# Sheet2.net
KiCad netlist of a schematic drawn in Altium Designer
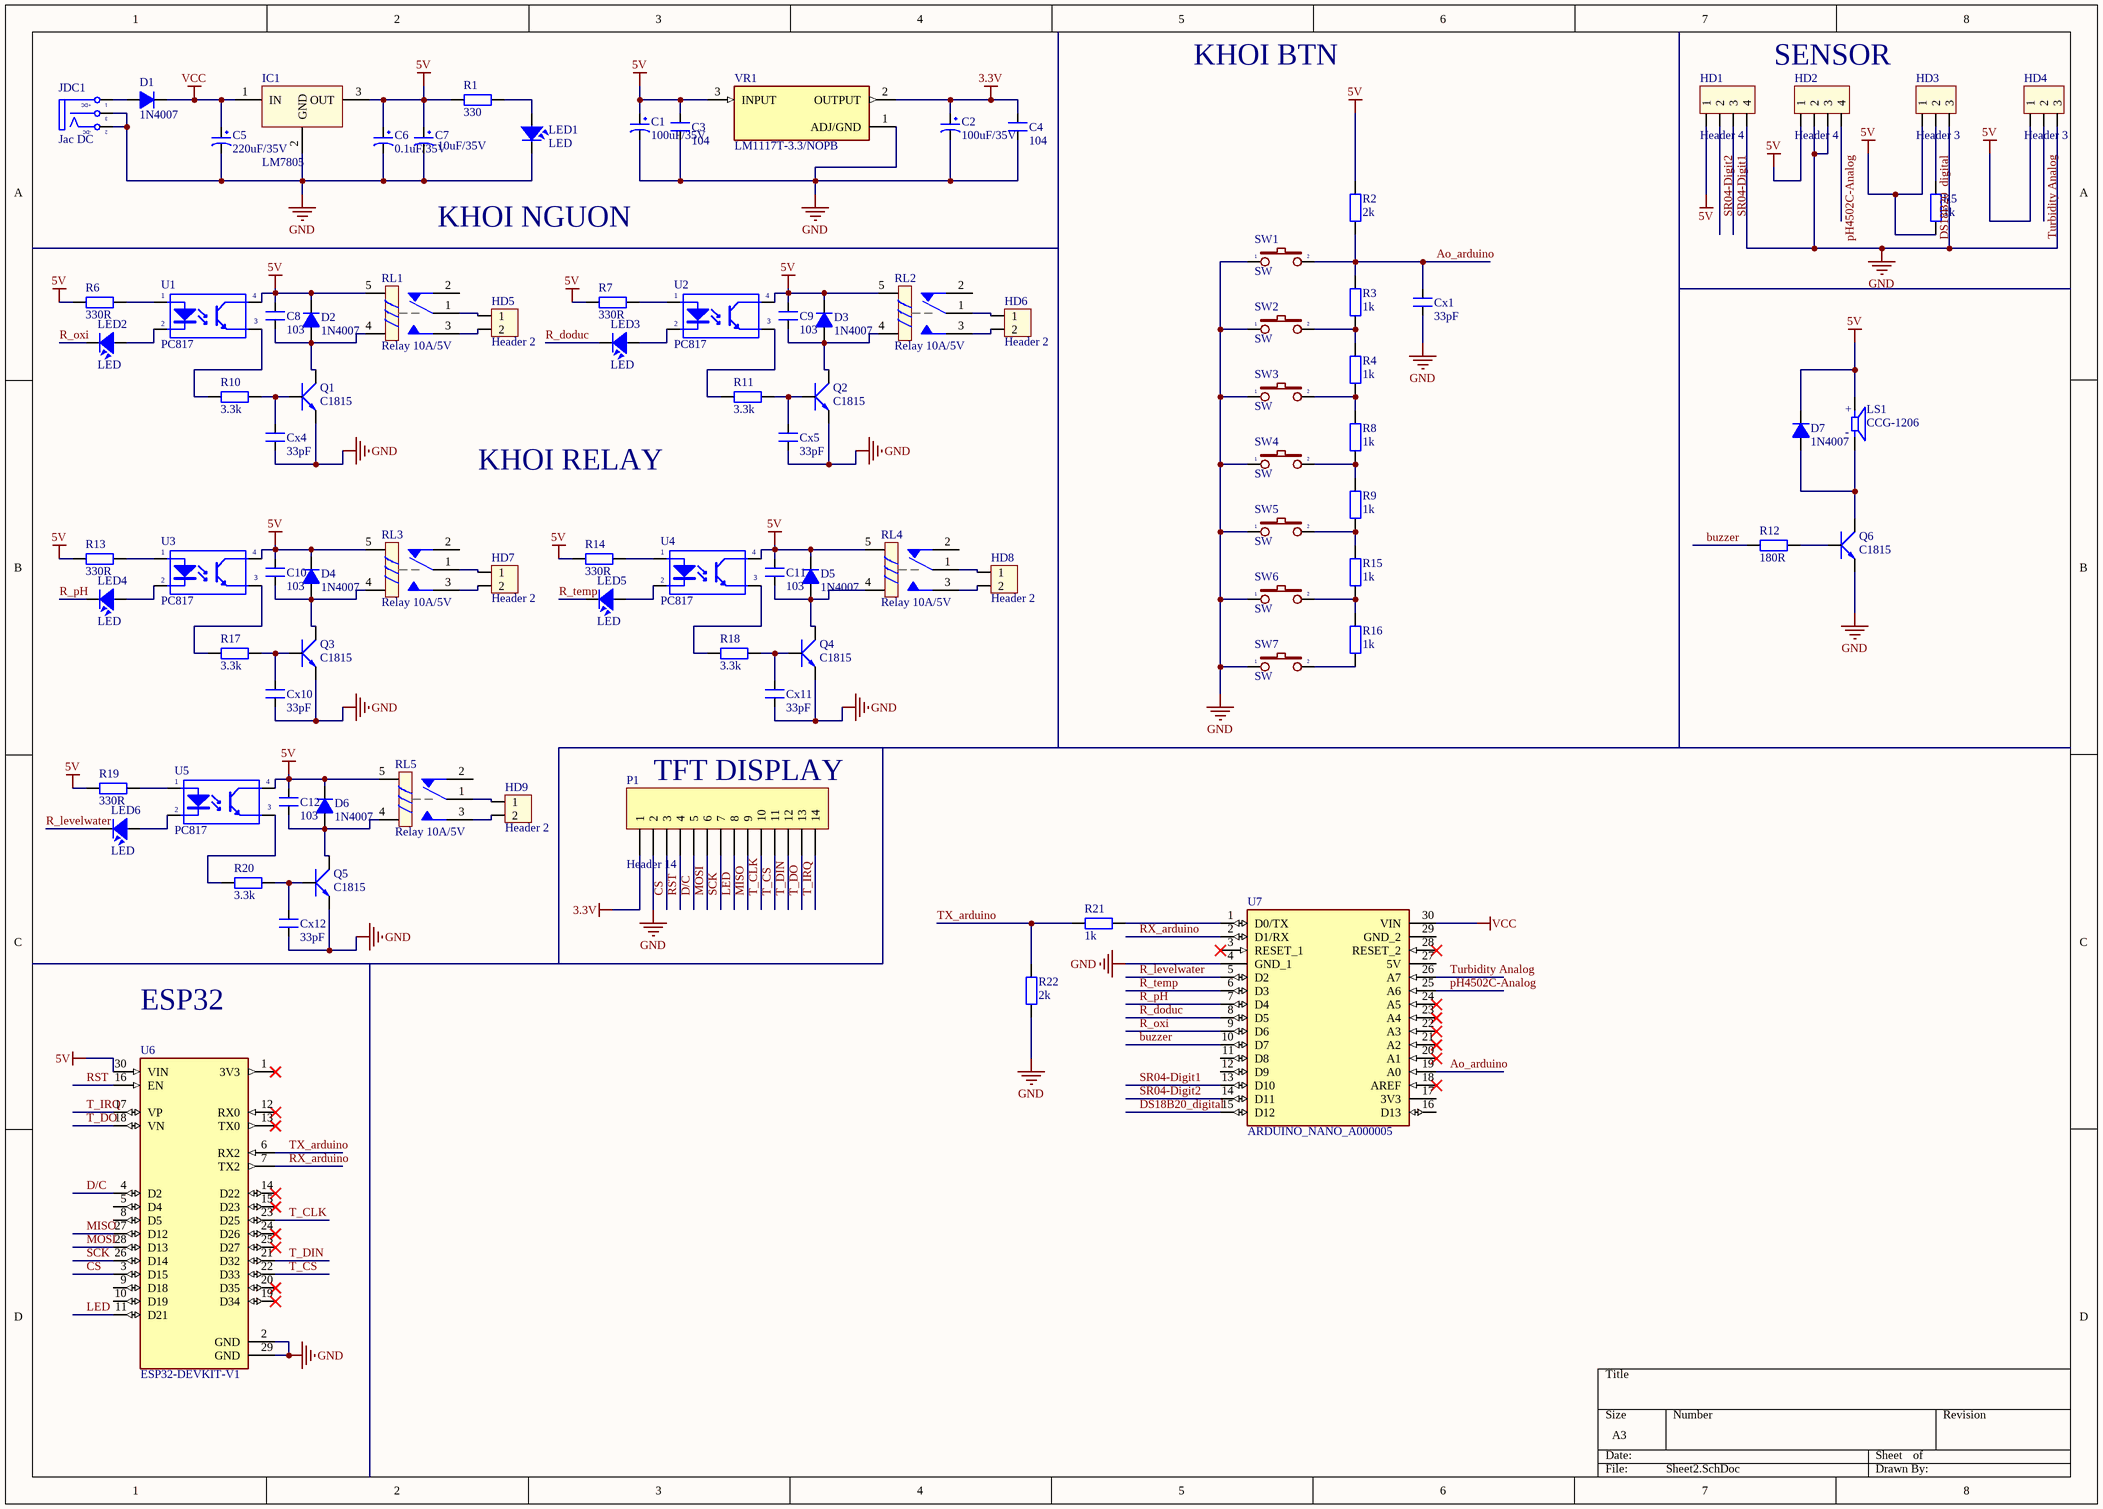
[diagram p0: Sheet2.SchDoc]

(export (version "E")
  (design (tool "Eeschema 10.0.6"))
  (components
    (comp (ref "C1")
      (value "100uF/35V")
      (footprint "CP1.5/3.4")
      (description "Cap 100uF/35V - 470uF/16V")
      (libsource (lib "syhaunguyen") (part "CP3"))
    )
    (comp (ref "C2")
      (value "100uF/35V")
      (footprint "CP1.5/3.4")
      (description "Cap 100uF/35V - 470uF/16V")
      (libsource (lib "syhaunguyen") (part "CP3"))
    )
    (comp (ref "C3")
      (value "104")
      (footprint "CN2")
      (description "Cap np 104 => 105pF")
      (libsource (lib "syhaunguyen") (part "CN2"))
    )
    (comp (ref "C4")
      (value "104")
      (footprint "CN2")
      (description "Cap np 104 => 105pF")
      (libsource (lib "syhaunguyen") (part "CN2"))
    )
    (comp (ref "C5")
      (value "220uF/35V")
      (footprint "CP1.5/3.4")
      (description "Cap 100uF/35V - 470uF/16V")
      (libsource (lib "syhaunguyen") (part "CP3"))
    )
    (comp (ref "C6")
      (value "0.1uF/35V")
      (footprint "CP1.5/3.4")
      (description "Cap 100uF/35V - 470uF/16V")
      (libsource (lib "syhaunguyen") (part "CP3"))
    )
    (comp (ref "C7")
      (value "10uF/35V")
      (footprint "CP1.5/3.4")
      (description "Cap 100uF/35V - 470uF/16V")
      (libsource (lib "syhaunguyen") (part "CP3"))
    )
    (comp (ref "C8")
      (value "103")
      (footprint "CN1.5")
      (description "Cap np 682pF => 104pF")
      (libsource (lib "syhaunguyen") (part "CN1.5"))
    )
    (comp (ref "C9")
      (value "103")
      (footprint "CN1.5")
      (description "Cap np 682pF => 104pF")
      (libsource (lib "syhaunguyen") (part "CN1.5"))
    )
    (comp (ref "C10")
      (value "103")
      (footprint "CN1.5")
      (description "Cap np 682pF => 104pF")
      (libsource (lib "syhaunguyen") (part "CN1.5"))
    )
    (comp (ref "C11")
      (value "103")
      (footprint "CN1.5")
      (description "Cap np 682pF => 104pF")
      (libsource (lib "syhaunguyen") (part "CN1.5"))
    )
    (comp (ref "C12")
      (value "103")
      (footprint "CN1.5")
      (description "Cap np 682pF => 104pF")
      (libsource (lib "syhaunguyen") (part "CN1.5"))
    )
    (comp (ref "Cx1")
      (value "33pF")
      (footprint "CN1")
      (description "Cremic For Xtal 1pF => 100pF")
      (libsource (lib "syhaunguyen") (part "CN0"))
    )
    (comp (ref "Cx4")
      (value "33pF")
      (footprint "CN1")
      (description "Cremic For Xtal 1pF => 100pF")
      (libsource (lib "syhaunguyen") (part "CN0"))
    )
    (comp (ref "Cx5")
      (value "33pF")
      (footprint "CN1")
      (description "Cremic For Xtal 1pF => 100pF")
      (libsource (lib "syhaunguyen") (part "CN0"))
    )
    (comp (ref "Cx10")
      (value "33pF")
      (footprint "CN1")
      (description "Cremic For Xtal 1pF => 100pF")
      (libsource (lib "syhaunguyen") (part "CN0"))
    )
    (comp (ref "Cx11")
      (value "33pF")
      (footprint "CN1")
      (description "Cremic For Xtal 1pF => 100pF")
      (libsource (lib "syhaunguyen") (part "CN0"))
    )
    (comp (ref "Cx12")
      (value "33pF")
      (footprint "CN1")
      (description "Cremic For Xtal 1pF => 100pF")
      (libsource (lib "syhaunguyen") (part "CN0"))
    )
    (comp (ref "D1")
      (value "1N4007")
      (footprint "D1A")
      (description "Diode 1A")
      (libsource (lib "syhaunguyen") (part "D1A"))
    )
    (comp (ref "D2")
      (value "1N4007")
      (footprint "D1A")
      (description "Diode 1A")
      (libsource (lib "syhaunguyen") (part "D1A"))
    )
    (comp (ref "D3")
      (value "1N4007")
      (footprint "D1A")
      (description "Diode 1A")
      (libsource (lib "syhaunguyen") (part "D1A"))
    )
    (comp (ref "D4")
      (value "1N4007")
      (footprint "D1A")
      (description "Diode 1A")
      (libsource (lib "syhaunguyen") (part "D1A"))
    )
    (comp (ref "D5")
      (value "1N4007")
      (footprint "D1A")
      (description "Diode 1A")
      (libsource (lib "syhaunguyen") (part "D1A"))
    )
    (comp (ref "D6")
      (value "1N4007")
      (footprint "D1A")
      (description "Diode 1A")
      (libsource (lib "syhaunguyen") (part "D1A"))
    )
    (comp (ref "D7")
      (value "1N4007")
      (footprint "D1A")
      (description "Diode 1A")
      (libsource (lib "syhaunguyen") (part "D1A"))
    )
    (comp (ref "HD1")
      (value "Header 4")
      (footprint "HED4")
      (description "Header 4 (Green)")
      (libsource (lib "syhaunguyen") (part "Hed4"))
    )
    (comp (ref "HD2")
      (value "Header 4")
      (footprint "HED4")
      (description "Header 4 (Green)")
      (libsource (lib "syhaunguyen") (part "Hed4"))
    )
    (comp (ref "HD3")
      (value "Header 3")
      (footprint "HED3")
      (description "Header 3 (Green)")
      (libsource (lib "syhaunguyen") (part "Hed3"))
    )
    (comp (ref "HD4")
      (value "Header 3")
      (footprint "HED3")
      (description "Header 3 (Green)")
      (libsource (lib "syhaunguyen") (part "Hed3"))
    )
    (comp (ref "HD5")
      (value "Header 2")
      (footprint "HED2")
      (description "Header 2 (Green)")
      (libsource (lib "syhaunguyen") (part "Hed2"))
    )
    (comp (ref "HD6")
      (value "Header 2")
      (footprint "HED2")
      (description "Header 2 (Green)")
      (libsource (lib "syhaunguyen") (part "Hed2"))
    )
    (comp (ref "HD7")
      (value "Header 2")
      (footprint "HED2")
      (description "Header 2 (Green)")
      (libsource (lib "syhaunguyen") (part "Hed2"))
    )
    (comp (ref "HD8")
      (value "Header 2")
      (footprint "HED2")
      (description "Header 2 (Green)")
      (libsource (lib "syhaunguyen") (part "Hed2"))
    )
    (comp (ref "HD9")
      (value "Header 2")
      (footprint "HED2")
      (description "Header 2 (Green)")
      (libsource (lib "syhaunguyen") (part "Hed2"))
    )
    (comp (ref "IC1")
      (value "LM7805")
      (footprint "QTO-220")
      (description "On ap +, from + 5 to + 24VDC")
      (libsource (lib "syhaunguyen") (part "LM78xx"))
    )
    (comp (ref "JDC1")
      (value "Jac DC")
      (footprint "DC-IN")
      (description "Jac DC input")
      (libsource (lib "syhaunguyen") (part "DCIN"))
    )
    (comp (ref "LED1")
      (value "LED")
      (footprint "LED-3")
      (description "LED Single colour Green and Red")
      (libsource (lib "syhaunguyen") (part "LED"))
    )
    (comp (ref "LED2")
      (value "LED")
      (footprint "LED-3")
      (description "LED Single colour Green and Red")
      (libsource (lib "syhaunguyen") (part "LED"))
    )
    (comp (ref "LED3")
      (value "LED")
      (footprint "LED-3")
      (description "LED Single colour Green and Red")
      (libsource (lib "syhaunguyen") (part "LED"))
    )
    (comp (ref "LED4")
      (value "LED")
      (footprint "LED-3")
      (description "LED Single colour Green and Red")
      (libsource (lib "syhaunguyen") (part "LED"))
    )
    (comp (ref "LED5")
      (value "LED")
      (footprint "LED-3")
      (description "LED Single colour Green and Red")
      (libsource (lib "syhaunguyen") (part "LED"))
    )
    (comp (ref "LED6")
      (value "LED")
      (footprint "LED-3")
      (description "LED Single colour Green and Red")
      (libsource (lib "syhaunguyen") (part "LED"))
    )
    (comp (ref "LS1")
      (value "CCG-1206")
      (footprint "CUI_CCG-1206")
      (description "12 mm, 5 V, 85 dB, Through Hole, Sealed, Magnetic Audio Transducer Buzzer")
      (libsource (lib "CCG-1206") (part "CCG-1206"))
    )
    (comp (ref "P1")
      (value "Header 14")
      (footprint "HDR1X14")
      (description "Header, 14-Pin")
      (fields (field (name "PUBLISHER") "Altium Limited"))
      (libsource (lib "Library AL") (part "Header 14"))
    )
    (comp (ref "Q1")
      (value "C1815")
      (footprint "QTO-92")
      (description "NPN 600mW, ECB")
      (libsource (lib "syhaunguyen") (part "C1815"))
    )
    (comp (ref "Q2")
      (value "C1815")
      (footprint "QTO-92")
      (description "NPN 600mW, ECB")
      (libsource (lib "syhaunguyen") (part "C1815"))
    )
    (comp (ref "Q3")
      (value "C1815")
      (footprint "QTO-92")
      (description "NPN 600mW, ECB")
      (libsource (lib "syhaunguyen") (part "C1815"))
    )
    (comp (ref "Q4")
      (value "C1815")
      (footprint "QTO-92")
      (description "NPN 600mW, ECB")
      (libsource (lib "syhaunguyen") (part "C1815"))
    )
    (comp (ref "Q5")
      (value "C1815")
      (footprint "QTO-92")
      (description "NPN 600mW, ECB")
      (libsource (lib "syhaunguyen") (part "C1815"))
    )
    (comp (ref "Q6")
      (value "C1815")
      (footprint "QTO-92")
      (description "NPN 600mW, ECB")
      (libsource (lib "syhaunguyen") (part "C1815"))
    )
    (comp (ref "R1")
      (value "330")
      (footprint "R1/4W")
      (description "Resistor 1/4W")
      (libsource (lib "syhaunguyen") (part "R1/4W"))
    )
    (comp (ref "R2")
      (value "2k")
      (footprint "R1/4W")
      (description "Resistor 1/4W")
      (libsource (lib "syhaunguyen") (part "R1/4W"))
    )
    (comp (ref "R3")
      (value "1k")
      (footprint "R1/4W")
      (description "Resistor 1/4W")
      (libsource (lib "syhaunguyen") (part "R1/4W"))
    )
    (comp (ref "R4")
      (value "1k")
      (footprint "R1/4W")
      (description "Resistor 1/4W")
      (libsource (lib "syhaunguyen") (part "R1/4W"))
    )
    (comp (ref "R5")
      (value "1k")
      (footprint "R1/4W")
      (description "Resistor 1/4W")
      (libsource (lib "syhaunguyen") (part "R1/4W"))
    )
    (comp (ref "R6")
      (value "330R")
      (footprint "R1/4W")
      (description "Resistor 1/4W")
      (libsource (lib "syhaunguyen") (part "R1/4W"))
    )
    (comp (ref "R7")
      (value "330R")
      (footprint "R1/4W")
      (description "Resistor 1/4W")
      (libsource (lib "syhaunguyen") (part "R1/4W"))
    )
    (comp (ref "R8")
      (value "1k")
      (footprint "R1/4W")
      (description "Resistor 1/4W")
      (libsource (lib "syhaunguyen") (part "R1/4W"))
    )
    (comp (ref "R9")
      (value "1k")
      (footprint "R1/4W")
      (description "Resistor 1/4W")
      (libsource (lib "syhaunguyen") (part "R1/4W"))
    )
    (comp (ref "R10")
      (value "3.3k")
      (footprint "R1/4W")
      (description "Resistor 1/4W")
      (libsource (lib "syhaunguyen") (part "R1/4W"))
    )
    (comp (ref "R11")
      (value "3.3k")
      (footprint "R1/4W")
      (description "Resistor 1/4W")
      (libsource (lib "syhaunguyen") (part "R1/4W"))
    )
    (comp (ref "R12")
      (value "180R")
      (footprint "R1/4W")
      (description "Resistor 1/4W")
      (libsource (lib "syhaunguyen") (part "R1/4W"))
    )
    (comp (ref "R13")
      (value "330R")
      (footprint "R1/4W")
      (description "Resistor 1/4W")
      (libsource (lib "syhaunguyen") (part "R1/4W"))
    )
    (comp (ref "R14")
      (value "330R")
      (footprint "R1/4W")
      (description "Resistor 1/4W")
      (libsource (lib "syhaunguyen") (part "R1/4W"))
    )
    (comp (ref "R15")
      (value "1k")
      (footprint "R1/4W")
      (description "Resistor 1/4W")
      (libsource (lib "syhaunguyen") (part "R1/4W"))
    )
    (comp (ref "R16")
      (value "1k")
      (footprint "R1/4W")
      (description "Resistor 1/4W")
      (libsource (lib "syhaunguyen") (part "R1/4W"))
    )
    (comp (ref "R17")
      (value "3.3k")
      (footprint "R1/4W")
      (description "Resistor 1/4W")
      (libsource (lib "syhaunguyen") (part "R1/4W"))
    )
    (comp (ref "R18")
      (value "3.3k")
      (footprint "R1/4W")
      (description "Resistor 1/4W")
      (libsource (lib "syhaunguyen") (part "R1/4W"))
    )
    (comp (ref "R19")
      (value "330R")
      (footprint "R1/4W")
      (description "Resistor 1/4W")
      (libsource (lib "syhaunguyen") (part "R1/4W"))
    )
    (comp (ref "R20")
      (value "3.3k")
      (footprint "R1/4W")
      (description "Resistor 1/4W")
      (libsource (lib "syhaunguyen") (part "R1/4W"))
    )
    (comp (ref "R21")
      (value "1k")
      (footprint "R1/4W")
      (description "Resistor 1/4W")
      (libsource (lib "Library AL") (part "R1/4W"))
    )
    (comp (ref "R22")
      (value "2k")
      (footprint "R1/4W")
      (description "Resistor 1/4W")
      (libsource (lib "Library AL") (part "R1/4W"))
    )
    (comp (ref "RL1")
      (value "Relay 10A/5V")
      (footprint "RL_SPDT_10A")
      (description "Relay SPDT,10A - 12VDC 5 Pin")
      (libsource (lib "syhaunguyen") (part "Relay 1"))
    )
    (comp (ref "RL2")
      (value "Relay 10A/5V")
      (footprint "RL_SPDT_10A")
      (description "Relay SPDT,10A - 12VDC 5 Pin")
      (libsource (lib "syhaunguyen") (part "Relay 1"))
    )
    (comp (ref "RL3")
      (value "Relay 10A/5V")
      (footprint "RL_SPDT_10A")
      (description "Relay SPDT,10A - 12VDC 5 Pin")
      (libsource (lib "syhaunguyen") (part "Relay 1"))
    )
    (comp (ref "RL4")
      (value "Relay 10A/5V")
      (footprint "RL_SPDT_10A")
      (description "Relay SPDT,10A - 12VDC 5 Pin")
      (libsource (lib "syhaunguyen") (part "Relay 1"))
    )
    (comp (ref "RL5")
      (value "Relay 10A/5V")
      (footprint "RL_SPDT_10A")
      (description "Relay SPDT,10A - 12VDC 5 Pin")
      (libsource (lib "syhaunguyen") (part "Relay 1"))
    )
    (comp (ref "SW1")
      (value "SW")
      (footprint "SW2")
      (description "Switch button 2 pin")
      (libsource (lib "Library AL") (part "SW2"))
    )
    (comp (ref "SW2")
      (value "SW")
      (footprint "SW2")
      (description "Switch button 2 pin")
      (libsource (lib "Library AL") (part "SW2"))
    )
    (comp (ref "SW3")
      (value "SW")
      (footprint "SW2")
      (description "Switch button 2 pin")
      (libsource (lib "Library AL") (part "SW2"))
    )
    (comp (ref "SW4")
      (value "SW")
      (footprint "SW2")
      (description "Switch button 2 pin")
      (libsource (lib "Library AL") (part "SW2"))
    )
    (comp (ref "SW5")
      (value "SW")
      (footprint "SW2")
      (description "Switch button 2 pin")
      (libsource (lib "Library AL") (part "SW2"))
    )
    (comp (ref "SW6")
      (value "SW")
      (footprint "SW2")
      (description "Switch button 2 pin")
      (libsource (lib "Library AL") (part "SW2"))
    )
    (comp (ref "SW7")
      (value "SW")
      (footprint "SW2")
      (description "Switch button 2 pin")
      (libsource (lib "Library AL") (part "SW2"))
    )
    (comp (ref "U1")
      (value "PC817")
      (footprint "DIP4/W0.3")
      (description "Single Opto")
      (libsource (lib "syhaunguyen") (part "PC817"))
    )
    (comp (ref "U2")
      (value "PC817")
      (footprint "DIP4/W0.3")
      (description "Single Opto")
      (libsource (lib "syhaunguyen") (part "PC817"))
    )
    (comp (ref "U3")
      (value "PC817")
      (footprint "DIP4/W0.3")
      (description "Single Opto")
      (libsource (lib "syhaunguyen") (part "PC817"))
    )
    (comp (ref "U4")
      (value "PC817")
      (footprint "DIP4/W0.3")
      (description "Single Opto")
      (libsource (lib "syhaunguyen") (part "PC817"))
    )
    (comp (ref "U5")
      (value "PC817")
      (footprint "DIP4/W0.3")
      (description "Single Opto")
      (libsource (lib "syhaunguyen") (part "PC817"))
    )
    (comp (ref "U6")
      (value "ESP32-DEVKIT-V1")
      (footprint "MODULE_ESP32_DEVKIT_V1")
      (fields (field (name "MF") "Do it"))
      (libsource (lib "ESP32-DEVKIT-V1") (part "ESP32-DEVKIT-V1"))
    )
    (comp (ref "U7")
      (value "ARDUINO_NANO_A000005")
      (footprint "MODULE_ARDUINO_NANO_A000005")
      (description "ATSAMD21G18A Arduino Nano 33 IoT series ARMÂ® CortexÂ®-M0+ MCU 32-Bit Embedded Evaluation Board")
      (fields (field (name "MF") "Arduino") (field (name "MP") "ARDUINO NANO A000005"))
      (libsource (lib "ARDUINO_NANO_A000005") (part "ARDUINO_NANO_A000005"))
    )
    (comp (ref "VR1")
      (value "LM1117T-3.3/NOPB")
      (footprint "TO254P1054X470X1955-3")
      (description "800-mA 15-V linear voltage regulator")
      (fields (field (name "MF") "Texas Instruments"))
      (libsource (lib "LM1117T-3.3_NOPB") (part "LM1117T-3.3/NOPB"))
    )
  )
  (nets
    (net (code "2") (name "/Ao_arduino") (class "Default")
      (node (ref "Cx1") (pin "1") (pinfunction "1_1") (pintype "passive"))
      (node (ref "R2") (pin "1") (pinfunction "1_1") (pintype "passive"))
      (node (ref "R3") (pin "2") (pinfunction "2_2") (pintype "passive"))
      (node (ref "SW1") (pin "2") (pinfunction "2_2") (pintype "passive"))
      (node (ref "U7") (pin "19") (pinfunction "A0_19") (pintype "input"))
    )
    (net (code "3") (name "/CS") (class "Default")
      (node (ref "P1") (pin "3") (pinfunction "3_3") (pintype "passive"))
      (node (ref "U6") (pin "3") (pinfunction "D15_3") (pintype "bidirectional"))
    )
    (net (code "4") (name "/DS18B20_digital") (class "Default")
      (node (ref "HD3") (pin "2") (pinfunction "2_2") (pintype "passive"))
      (node (ref "R5") (pin "2") (pinfunction "2_2") (pintype "passive"))
      (node (ref "U7") (pin "15") (pinfunction "D12_15") (pintype "bidirectional"))
    )
    (net (code "5") (name "/D{slash}C") (class "Default")
      (node (ref "P1") (pin "5") (pinfunction "5_5") (pintype "passive"))
      (node (ref "U6") (pin "4") (pinfunction "D2_4") (pintype "bidirectional"))
    )
    (net (code "6") (name "/LED") (class "Default")
      (node (ref "P1") (pin "8") (pinfunction "8_8") (pintype "passive"))
      (node (ref "U6") (pin "11") (pinfunction "D21_11") (pintype "bidirectional"))
    )
    (net (code "7") (name "/MISO") (class "Default")
      (node (ref "P1") (pin "9") (pinfunction "9_9") (pintype "passive"))
      (node (ref "U6") (pin "27") (pinfunction "D12_27") (pintype "bidirectional"))
    )
    (net (code "8") (name "/MOSI") (class "Default")
      (node (ref "P1") (pin "6") (pinfunction "6_6") (pintype "passive"))
      (node (ref "U6") (pin "28") (pinfunction "D13_28") (pintype "bidirectional"))
    )
    (net (code "9") (name "/RST") (class "Default")
      (node (ref "P1") (pin "4") (pinfunction "4_4") (pintype "passive"))
      (node (ref "U6") (pin "16") (pinfunction "EN_16") (pintype "input"))
    )
    (net (code "10") (name "/RX_arduino") (class "Default")
      (node (ref "U6") (pin "7") (pinfunction "TX2_7") (pintype "output"))
      (node (ref "U7") (pin "2") (pinfunction "D1/RX_2") (pintype "bidirectional"))
    )
    (net (code "11") (name "/R_doduc") (class "Default")
      (node (ref "LED3") (pin "2") (pinfunction "2_2") (pintype "passive"))
      (node (ref "U7") (pin "8") (pinfunction "D5_8") (pintype "bidirectional"))
    )
    (net (code "12") (name "/R_levelwater") (class "Default")
      (node (ref "LED6") (pin "2") (pinfunction "2_2") (pintype "passive"))
      (node (ref "U7") (pin "5") (pinfunction "D2_5") (pintype "bidirectional"))
    )
    (net (code "13") (name "/R_oxi") (class "Default")
      (node (ref "LED2") (pin "2") (pinfunction "2_2") (pintype "passive"))
      (node (ref "U7") (pin "9") (pinfunction "D6_9") (pintype "bidirectional"))
    )
    (net (code "14") (name "/R_pH") (class "Default")
      (node (ref "LED4") (pin "2") (pinfunction "2_2") (pintype "passive"))
      (node (ref "U7") (pin "7") (pinfunction "D4_7") (pintype "bidirectional"))
    )
    (net (code "15") (name "/R_temp") (class "Default")
      (node (ref "LED5") (pin "2") (pinfunction "2_2") (pintype "passive"))
      (node (ref "U7") (pin "6") (pinfunction "D3_6") (pintype "bidirectional"))
    )
    (net (code "16") (name "/SCK") (class "Default")
      (node (ref "P1") (pin "7") (pinfunction "7_7") (pintype "passive"))
      (node (ref "U6") (pin "26") (pinfunction "D14_26") (pintype "bidirectional"))
    )
    (net (code "17") (name "/SR04-Digit1") (class "Default")
      (node (ref "HD1") (pin "3") (pinfunction "3_3") (pintype "passive"))
      (node (ref "U7") (pin "13") (pinfunction "D10_13") (pintype "bidirectional"))
    )
    (net (code "18") (name "/SR04-Digit2") (class "Default")
      (node (ref "HD1") (pin "2") (pinfunction "2_2") (pintype "passive"))
      (node (ref "U7") (pin "14") (pinfunction "D11_14") (pintype "bidirectional"))
    )
    (net (code "19") (name "/TX_arduino") (class "Default")
      (node (ref "R21") (pin "1") (pinfunction "1_1") (pintype "passive"))
      (node (ref "R22") (pin "1") (pinfunction "1_1") (pintype "passive"))
      (node (ref "U6") (pin "6") (pinfunction "RX2_6") (pintype "input"))
    )
    (net (code "20") (name "/T_CLK") (class "Default")
      (node (ref "P1") (pin "10") (pinfunction "10_10") (pintype "passive"))
      (node (ref "U6") (pin "23") (pinfunction "D25_23") (pintype "bidirectional"))
    )
    (net (code "21") (name "/T_CS") (class "Default")
      (node (ref "P1") (pin "11") (pinfunction "11_11") (pintype "passive"))
      (node (ref "U6") (pin "22") (pinfunction "D33_22") (pintype "bidirectional"))
    )
    (net (code "22") (name "/T_DIN") (class "Default")
      (node (ref "P1") (pin "12") (pinfunction "12_12") (pintype "passive"))
      (node (ref "U6") (pin "21") (pinfunction "D32_21") (pintype "bidirectional"))
    )
    (net (code "23") (name "/T_DO") (class "Default")
      (node (ref "P1") (pin "13") (pinfunction "13_13") (pintype "passive"))
      (node (ref "U6") (pin "18") (pinfunction "VN_18") (pintype "bidirectional"))
    )
    (net (code "24") (name "/T_IRQ") (class "Default")
      (node (ref "P1") (pin "14") (pinfunction "14_14") (pintype "passive"))
      (node (ref "U6") (pin "17") (pinfunction "VP_17") (pintype "bidirectional"))
    )
    (net (code "25") (name "/Turbidity Analog") (class "Default")
      (node (ref "HD4") (pin "2") (pinfunction "2_2") (pintype "passive"))
      (node (ref "U7") (pin "26") (pinfunction "A7_26") (pintype "input"))
    )
    (net (code "26") (name "/buzzer") (class "Default")
      (node (ref "R12") (pin "2") (pinfunction "2_2") (pintype "passive"))
      (node (ref "U7") (pin "10") (pinfunction "D7_10") (pintype "bidirectional"))
    )
    (net (code "27") (name "/pH4502C-Analog") (class "Default")
      (node (ref "HD2") (pin "4") (pinfunction "4_4") (pintype "passive"))
      (node (ref "U7") (pin "25") (pinfunction "A6_25") (pintype "input"))
    )
    (net (code "29") (name "3.3V") (class "Default")
      (node (ref "C2") (pin "1") (pinfunction "1_1") (pintype "passive"))
      (node (ref "C4") (pin "2") (pinfunction "2_2") (pintype "passive"))
      (node (ref "P1") (pin "1") (pinfunction "1_1") (pintype "passive"))
      (node (ref "VR1") (pin "2") (pinfunction "OUTPUT_2") (pintype "output"))
    )
    (net (code "30") (name "5V") (class "Default")
      (node (ref "C1") (pin "1") (pinfunction "1_1") (pintype "passive"))
      (node (ref "C10") (pin "1") (pinfunction "1_1") (pintype "passive"))
      (node (ref "C11") (pin "1") (pinfunction "1_1") (pintype "passive"))
      (node (ref "C12") (pin "1") (pinfunction "1_1") (pintype "passive"))
      (node (ref "C3") (pin "2") (pinfunction "2_2") (pintype "passive"))
      (node (ref "C6") (pin "1") (pinfunction "1_1") (pintype "passive"))
      (node (ref "C7") (pin "1") (pinfunction "1_1") (pintype "passive"))
      (node (ref "C8") (pin "1") (pinfunction "1_1") (pintype "passive"))
      (node (ref "C9") (pin "1") (pinfunction "1_1") (pintype "passive"))
      (node (ref "D2") (pin "2") (pinfunction "K_2") (pintype "passive"))
      (node (ref "D3") (pin "2") (pinfunction "K_2") (pintype "passive"))
      (node (ref "D4") (pin "2") (pinfunction "K_2") (pintype "passive"))
      (node (ref "D5") (pin "2") (pinfunction "K_2") (pintype "passive"))
      (node (ref "D6") (pin "2") (pinfunction "K_2") (pintype "passive"))
      (node (ref "D7") (pin "2") (pinfunction "K_2") (pintype "passive"))
      (node (ref "HD1") (pin "1") (pinfunction "1_1") (pintype "passive"))
      (node (ref "HD2") (pin "1") (pinfunction "1_1") (pintype "passive"))
      (node (ref "HD3") (pin "1") (pinfunction "1_1") (pintype "passive"))
      (node (ref "HD4") (pin "1") (pinfunction "1_1") (pintype "passive"))
      (node (ref "IC1") (pin "3") (pinfunction "OUT_3") (pintype "passive"))
      (node (ref "LS1") (pin "P") (pinfunction "P_P") (pintype "passive"))
      (node (ref "R1") (pin "1") (pinfunction "1_1") (pintype "passive"))
      (node (ref "R13") (pin "1") (pinfunction "1_1") (pintype "passive"))
      (node (ref "R14") (pin "1") (pinfunction "1_1") (pintype "passive"))
      (node (ref "R19") (pin "1") (pinfunction "1_1") (pintype "passive"))
      (node (ref "R2") (pin "2") (pinfunction "2_2") (pintype "passive"))
      (node (ref "R5") (pin "1") (pinfunction "1_1") (pintype "passive"))
      (node (ref "R6") (pin "1") (pinfunction "1_1") (pintype "passive"))
      (node (ref "R7") (pin "1") (pinfunction "1_1") (pintype "passive"))
      (node (ref "RL1") (pin "5") (pinfunction "5_5") (pintype "passive"))
      (node (ref "RL2") (pin "5") (pinfunction "5_5") (pintype "passive"))
      (node (ref "RL3") (pin "5") (pinfunction "5_5") (pintype "passive"))
      (node (ref "RL4") (pin "5") (pinfunction "5_5") (pintype "passive"))
      (node (ref "RL5") (pin "5") (pinfunction "5_5") (pintype "passive"))
      (node (ref "U1") (pin "4") (pinfunction "C_4") (pintype "passive"))
      (node (ref "U2") (pin "4") (pinfunction "C_4") (pintype "passive"))
      (node (ref "U3") (pin "4") (pinfunction "C_4") (pintype "passive"))
      (node (ref "U4") (pin "4") (pinfunction "C_4") (pintype "passive"))
      (node (ref "U5") (pin "4") (pinfunction "C_4") (pintype "passive"))
      (node (ref "U6") (pin "30") (pinfunction "VIN_30") (pintype "input"))
      (node (ref "VR1") (pin "3") (pinfunction "INPUT_3") (pintype "input"))
    )
    (net (code "31") (name "GND") (class "Default")
      (node (ref "C1") (pin "2") (pinfunction "2_2") (pintype "passive"))
      (node (ref "C2") (pin "2") (pinfunction "2_2") (pintype "passive"))
      (node (ref "C3") (pin "1") (pinfunction "1_1") (pintype "passive"))
      (node (ref "C4") (pin "1") (pinfunction "1_1") (pintype "passive"))
      (node (ref "C5") (pin "2") (pinfunction "2_2") (pintype "passive"))
      (node (ref "C6") (pin "2") (pinfunction "2_2") (pintype "passive"))
      (node (ref "C7") (pin "2") (pinfunction "2_2") (pintype "passive"))
      (node (ref "Cx1") (pin "2") (pinfunction "2_2") (pintype "passive"))
      (node (ref "Cx10") (pin "2") (pinfunction "2_2") (pintype "passive"))
      (node (ref "Cx11") (pin "2") (pinfunction "2_2") (pintype "passive"))
      (node (ref "Cx12") (pin "2") (pinfunction "2_2") (pintype "passive"))
      (node (ref "Cx4") (pin "2") (pinfunction "2_2") (pintype "passive"))
      (node (ref "Cx5") (pin "2") (pinfunction "2_2") (pintype "passive"))
      (node (ref "HD1") (pin "4") (pinfunction "4_4") (pintype "passive"))
      (node (ref "HD2") (pin "2") (pinfunction "2_2") (pintype "passive"))
      (node (ref "HD2") (pin "3") (pinfunction "3_3") (pintype "passive"))
      (node (ref "HD3") (pin "3") (pinfunction "3_3") (pintype "passive"))
      (node (ref "HD4") (pin "3") (pinfunction "3_3") (pintype "passive"))
      (node (ref "IC1") (pin "2") (pinfunction "GND_2") (pintype "passive"))
      (node (ref "JDC1") (pin "2") (pinfunction "TN_2") (pintype "passive"))
      (node (ref "JDC1") (pin "3") (pinfunction "S_3") (pintype "power_in"))
      (node (ref "LED1") (pin "2") (pinfunction "2_2") (pintype "passive"))
      (node (ref "P1") (pin "2") (pinfunction "2_2") (pintype "passive"))
      (node (ref "Q1") (pin "1") (pinfunction "E_1") (pintype "passive"))
      (node (ref "Q2") (pin "1") (pinfunction "E_1") (pintype "passive"))
      (node (ref "Q3") (pin "1") (pinfunction "E_1") (pintype "passive"))
      (node (ref "Q4") (pin "1") (pinfunction "E_1") (pintype "passive"))
      (node (ref "Q5") (pin "1") (pinfunction "E_1") (pintype "passive"))
      (node (ref "Q6") (pin "1") (pinfunction "E_1") (pintype "passive"))
      (node (ref "R22") (pin "2") (pinfunction "2_2") (pintype "passive"))
      (node (ref "SW1") (pin "1") (pinfunction "1_1") (pintype "passive"))
      (node (ref "SW2") (pin "1") (pinfunction "1_1") (pintype "passive"))
      (node (ref "SW3") (pin "1") (pinfunction "1_1") (pintype "passive"))
      (node (ref "SW4") (pin "1") (pinfunction "1_1") (pintype "passive"))
      (node (ref "SW5") (pin "1") (pinfunction "1_1") (pintype "passive"))
      (node (ref "SW6") (pin "1") (pinfunction "1_1") (pintype "passive"))
      (node (ref "SW7") (pin "1") (pinfunction "1_1") (pintype "passive"))
      (node (ref "U6") (pin "2") (pinfunction "GND_2") (pintype "power_in"))
      (node (ref "U6") (pin "29") (pinfunction "GND_29") (pintype "power_in"))
      (node (ref "U7") (pin "4") (pinfunction "GND_1_4") (pintype "power_in"))
      (node (ref "VR1") (pin "1") (pinfunction "ADJ/GND_1") (pintype "power_in"))
    )
    (net (code "32") (name "Net-(D1-A)") (class "Default")
      (node (ref "D1") (pin "1") (pinfunction "A_1") (pintype "passive"))
      (node (ref "JDC1") (pin "1") (pinfunction "T_1") (pintype "passive"))
    )
    (net (code "33") (name "Net-(D2-A)") (class "Default")
      (node (ref "C8") (pin "2") (pinfunction "2_2") (pintype "passive"))
      (node (ref "D2") (pin "1") (pinfunction "A_1") (pintype "passive"))
      (node (ref "Q1") (pin "2") (pinfunction "C_2") (pintype "passive"))
      (node (ref "RL1") (pin "4") (pinfunction "4_4") (pintype "passive"))
    )
    (net (code "34") (name "Net-(D3-A)") (class "Default")
      (node (ref "C9") (pin "2") (pinfunction "2_2") (pintype "passive"))
      (node (ref "D3") (pin "1") (pinfunction "A_1") (pintype "passive"))
      (node (ref "Q2") (pin "2") (pinfunction "C_2") (pintype "passive"))
      (node (ref "RL2") (pin "4") (pinfunction "4_4") (pintype "passive"))
    )
    (net (code "35") (name "Net-(D4-A)") (class "Default")
      (node (ref "C10") (pin "2") (pinfunction "2_2") (pintype "passive"))
      (node (ref "D4") (pin "1") (pinfunction "A_1") (pintype "passive"))
      (node (ref "Q3") (pin "2") (pinfunction "C_2") (pintype "passive"))
      (node (ref "RL3") (pin "4") (pinfunction "4_4") (pintype "passive"))
    )
    (net (code "36") (name "Net-(D5-A)") (class "Default")
      (node (ref "C11") (pin "2") (pinfunction "2_2") (pintype "passive"))
      (node (ref "D5") (pin "1") (pinfunction "A_1") (pintype "passive"))
      (node (ref "Q4") (pin "2") (pinfunction "C_2") (pintype "passive"))
      (node (ref "RL4") (pin "4") (pinfunction "4_4") (pintype "passive"))
    )
    (net (code "37") (name "Net-(D6-A)") (class "Default")
      (node (ref "C12") (pin "2") (pinfunction "2_2") (pintype "passive"))
      (node (ref "D6") (pin "1") (pinfunction "A_1") (pintype "passive"))
      (node (ref "Q5") (pin "2") (pinfunction "C_2") (pintype "passive"))
      (node (ref "RL5") (pin "4") (pinfunction "4_4") (pintype "passive"))
    )
    (net (code "38") (name "Net-(D7-A)") (class "Default")
      (node (ref "D7") (pin "1") (pinfunction "A_1") (pintype "passive"))
      (node (ref "LS1") (pin "M") (pinfunction "M_M") (pintype "passive"))
      (node (ref "Q6") (pin "2") (pinfunction "C_2") (pintype "passive"))
    )
    (net (code "39") (name "Net-(HD5-Pad1)") (class "Default")
      (node (ref "HD5") (pin "1") (pinfunction "1_1") (pintype "passive"))
      (node (ref "RL1") (pin "1") (pinfunction "1_1") (pintype "passive"))
    )
    (net (code "40") (name "Net-(HD5-Pad2)") (class "Default")
      (node (ref "HD5") (pin "2") (pinfunction "2_2") (pintype "passive"))
      (node (ref "RL1") (pin "3") (pinfunction "3_3") (pintype "passive"))
    )
    (net (code "41") (name "Net-(HD6-Pad1)") (class "Default")
      (node (ref "HD6") (pin "1") (pinfunction "1_1") (pintype "passive"))
      (node (ref "RL2") (pin "1") (pinfunction "1_1") (pintype "passive"))
    )
    (net (code "42") (name "Net-(HD6-Pad2)") (class "Default")
      (node (ref "HD6") (pin "2") (pinfunction "2_2") (pintype "passive"))
      (node (ref "RL2") (pin "3") (pinfunction "3_3") (pintype "passive"))
    )
    (net (code "43") (name "Net-(HD7-Pad1)") (class "Default")
      (node (ref "HD7") (pin "1") (pinfunction "1_1") (pintype "passive"))
      (node (ref "RL3") (pin "1") (pinfunction "1_1") (pintype "passive"))
    )
    (net (code "44") (name "Net-(HD7-Pad2)") (class "Default")
      (node (ref "HD7") (pin "2") (pinfunction "2_2") (pintype "passive"))
      (node (ref "RL3") (pin "3") (pinfunction "3_3") (pintype "passive"))
    )
    (net (code "45") (name "Net-(HD8-Pad1)") (class "Default")
      (node (ref "HD8") (pin "1") (pinfunction "1_1") (pintype "passive"))
      (node (ref "RL4") (pin "1") (pinfunction "1_1") (pintype "passive"))
    )
    (net (code "46") (name "Net-(HD8-Pad2)") (class "Default")
      (node (ref "HD8") (pin "2") (pinfunction "2_2") (pintype "passive"))
      (node (ref "RL4") (pin "3") (pinfunction "3_3") (pintype "passive"))
    )
    (net (code "47") (name "Net-(HD9-Pad1)") (class "Default")
      (node (ref "HD9") (pin "1") (pinfunction "1_1") (pintype "passive"))
      (node (ref "RL5") (pin "1") (pinfunction "1_1") (pintype "passive"))
    )
    (net (code "48") (name "Net-(HD9-Pad2)") (class "Default")
      (node (ref "HD9") (pin "2") (pinfunction "2_2") (pintype "passive"))
      (node (ref "RL5") (pin "3") (pinfunction "3_3") (pintype "passive"))
    )
    (net (code "49") (name "Net-(LED1-Pad1)") (class "Default")
      (node (ref "LED1") (pin "1") (pinfunction "1_1") (pintype "passive"))
      (node (ref "R1") (pin "2") (pinfunction "2_2") (pintype "passive"))
    )
    (net (code "50") (name "Net-(Q1-B)") (class "Default")
      (node (ref "Cx4") (pin "1") (pinfunction "1_1") (pintype "passive"))
      (node (ref "Q1") (pin "3") (pinfunction "B_3") (pintype "passive"))
      (node (ref "R10") (pin "1") (pinfunction "1_1") (pintype "passive"))
    )
    (net (code "51") (name "Net-(Q2-B)") (class "Default")
      (node (ref "Cx5") (pin "1") (pinfunction "1_1") (pintype "passive"))
      (node (ref "Q2") (pin "3") (pinfunction "B_3") (pintype "passive"))
      (node (ref "R11") (pin "1") (pinfunction "1_1") (pintype "passive"))
    )
    (net (code "52") (name "Net-(Q3-B)") (class "Default")
      (node (ref "Cx10") (pin "1") (pinfunction "1_1") (pintype "passive"))
      (node (ref "Q3") (pin "3") (pinfunction "B_3") (pintype "passive"))
      (node (ref "R17") (pin "1") (pinfunction "1_1") (pintype "passive"))
    )
    (net (code "53") (name "Net-(Q4-B)") (class "Default")
      (node (ref "Cx11") (pin "1") (pinfunction "1_1") (pintype "passive"))
      (node (ref "Q4") (pin "3") (pinfunction "B_3") (pintype "passive"))
      (node (ref "R18") (pin "1") (pinfunction "1_1") (pintype "passive"))
    )
    (net (code "54") (name "Net-(Q5-B)") (class "Default")
      (node (ref "Cx12") (pin "1") (pinfunction "1_1") (pintype "passive"))
      (node (ref "Q5") (pin "3") (pinfunction "B_3") (pintype "passive"))
      (node (ref "R20") (pin "1") (pinfunction "1_1") (pintype "passive"))
    )
    (net (code "55") (name "Net-(Q6-B)") (class "Default")
      (node (ref "Q6") (pin "3") (pinfunction "B_3") (pintype "passive"))
      (node (ref "R12") (pin "1") (pinfunction "1_1") (pintype "passive"))
    )
    (net (code "56") (name "Net-(R3-Pad1)") (class "Default")
      (node (ref "R3") (pin "1") (pinfunction "1_1") (pintype "passive"))
      (node (ref "R4") (pin "2") (pinfunction "2_2") (pintype "passive"))
      (node (ref "SW2") (pin "2") (pinfunction "2_2") (pintype "passive"))
    )
    (net (code "57") (name "Net-(R4-Pad1)") (class "Default")
      (node (ref "R4") (pin "1") (pinfunction "1_1") (pintype "passive"))
      (node (ref "R8") (pin "2") (pinfunction "2_2") (pintype "passive"))
      (node (ref "SW3") (pin "2") (pinfunction "2_2") (pintype "passive"))
    )
    (net (code "58") (name "Net-(R8-Pad1)") (class "Default")
      (node (ref "R8") (pin "1") (pinfunction "1_1") (pintype "passive"))
      (node (ref "R9") (pin "2") (pinfunction "2_2") (pintype "passive"))
      (node (ref "SW4") (pin "2") (pinfunction "2_2") (pintype "passive"))
    )
    (net (code "59") (name "Net-(R15-Pad1)") (class "Default")
      (node (ref "R15") (pin "1") (pinfunction "1_1") (pintype "passive"))
      (node (ref "R16") (pin "2") (pinfunction "2_2") (pintype "passive"))
      (node (ref "SW6") (pin "2") (pinfunction "2_2") (pintype "passive"))
    )
    (net (code "60") (name "Net-(R15-Pad2)") (class "Default")
      (node (ref "R15") (pin "2") (pinfunction "2_2") (pintype "passive"))
      (node (ref "R9") (pin "1") (pinfunction "1_1") (pintype "passive"))
      (node (ref "SW5") (pin "2") (pinfunction "2_2") (pintype "passive"))
    )
    (net (code "61") (name "Net-(R16-Pad1)") (class "Default")
      (node (ref "R16") (pin "1") (pinfunction "1_1") (pintype "passive"))
      (node (ref "SW7") (pin "2") (pinfunction "2_2") (pintype "passive"))
    )
    (net (code "62") (name "Net-(U1-A)") (class "Default")
      (node (ref "R6") (pin "2") (pinfunction "2_2") (pintype "passive"))
      (node (ref "U1") (pin "1") (pinfunction "A_1") (pintype "passive"))
    )
    (net (code "63") (name "Net-(U1-E)") (class "Default")
      (node (ref "R10") (pin "2") (pinfunction "2_2") (pintype "passive"))
      (node (ref "U1") (pin "3") (pinfunction "E_3") (pintype "passive"))
    )
    (net (code "64") (name "Net-(U1-K)") (class "Default")
      (node (ref "LED2") (pin "1") (pinfunction "1_1") (pintype "passive"))
      (node (ref "U1") (pin "2") (pinfunction "K_2") (pintype "passive"))
    )
    (net (code "65") (name "Net-(U2-A)") (class "Default")
      (node (ref "R7") (pin "2") (pinfunction "2_2") (pintype "passive"))
      (node (ref "U2") (pin "1") (pinfunction "A_1") (pintype "passive"))
    )
    (net (code "66") (name "Net-(U2-E)") (class "Default")
      (node (ref "R11") (pin "2") (pinfunction "2_2") (pintype "passive"))
      (node (ref "U2") (pin "3") (pinfunction "E_3") (pintype "passive"))
    )
    (net (code "67") (name "Net-(U2-K)") (class "Default")
      (node (ref "LED3") (pin "1") (pinfunction "1_1") (pintype "passive"))
      (node (ref "U2") (pin "2") (pinfunction "K_2") (pintype "passive"))
    )
    (net (code "68") (name "Net-(U3-A)") (class "Default")
      (node (ref "R13") (pin "2") (pinfunction "2_2") (pintype "passive"))
      (node (ref "U3") (pin "1") (pinfunction "A_1") (pintype "passive"))
    )
    (net (code "69") (name "Net-(U3-E)") (class "Default")
      (node (ref "R17") (pin "2") (pinfunction "2_2") (pintype "passive"))
      (node (ref "U3") (pin "3") (pinfunction "E_3") (pintype "passive"))
    )
    (net (code "70") (name "Net-(U3-K)") (class "Default")
      (node (ref "LED4") (pin "1") (pinfunction "1_1") (pintype "passive"))
      (node (ref "U3") (pin "2") (pinfunction "K_2") (pintype "passive"))
    )
    (net (code "71") (name "Net-(U4-A)") (class "Default")
      (node (ref "R14") (pin "2") (pinfunction "2_2") (pintype "passive"))
      (node (ref "U4") (pin "1") (pinfunction "A_1") (pintype "passive"))
    )
    (net (code "72") (name "Net-(U4-E)") (class "Default")
      (node (ref "R18") (pin "2") (pinfunction "2_2") (pintype "passive"))
      (node (ref "U4") (pin "3") (pinfunction "E_3") (pintype "passive"))
    )
    (net (code "73") (name "Net-(U4-K)") (class "Default")
      (node (ref "LED5") (pin "1") (pinfunction "1_1") (pintype "passive"))
      (node (ref "U4") (pin "2") (pinfunction "K_2") (pintype "passive"))
    )
    (net (code "74") (name "Net-(U5-A)") (class "Default")
      (node (ref "R19") (pin "2") (pinfunction "2_2") (pintype "passive"))
      (node (ref "U5") (pin "1") (pinfunction "A_1") (pintype "passive"))
    )
    (net (code "75") (name "Net-(U5-E)") (class "Default")
      (node (ref "R20") (pin "2") (pinfunction "2_2") (pintype "passive"))
      (node (ref "U5") (pin "3") (pinfunction "E_3") (pintype "passive"))
    )
    (net (code "76") (name "Net-(U5-K)") (class "Default")
      (node (ref "LED6") (pin "1") (pinfunction "1_1") (pintype "passive"))
      (node (ref "U5") (pin "2") (pinfunction "K_2") (pintype "passive"))
    )
    (net (code "77") (name "Net-(U7-D0{slash}TX)") (class "Default")
      (node (ref "R21") (pin "2") (pinfunction "2_2") (pintype "passive"))
      (node (ref "U7") (pin "1") (pinfunction "D0/TX_1") (pintype "bidirectional"))
    )
    (net (code "78") (name "VCC") (class "Default")
      (node (ref "C5") (pin "1") (pinfunction "1_1") (pintype "passive"))
      (node (ref "D1") (pin "2") (pinfunction "K_2") (pintype "passive"))
      (node (ref "IC1") (pin "1") (pinfunction "IN_1") (pintype "passive"))
      (node (ref "U7") (pin "30") (pinfunction "VIN_30") (pintype "power_in"))
    )
    (net (code "79") (name "unconnected-(RL1-Pad2)") (class "Default")
      (node (ref "RL1") (pin "2") (pinfunction "2_2") (pintype "passive"))
    )
    (net (code "80") (name "unconnected-(RL2-Pad2)") (class "Default")
      (node (ref "RL2") (pin "2") (pinfunction "2_2") (pintype "passive"))
    )
    (net (code "81") (name "unconnected-(RL3-Pad2)") (class "Default")
      (node (ref "RL3") (pin "2") (pinfunction "2_2") (pintype "passive"))
    )
    (net (code "82") (name "unconnected-(RL4-Pad2)") (class "Default")
      (node (ref "RL4") (pin "2") (pinfunction "2_2") (pintype "passive"))
    )
    (net (code "83") (name "unconnected-(RL5-Pad2)") (class "Default")
      (node (ref "RL5") (pin "2") (pinfunction "2_2") (pintype "passive"))
    )
    (net (code "84") (name "unconnected-(U6-3V3-Pad1)") (class "Default")
      (node (ref "U6") (pin "1") (pinfunction "3V3_1") (pintype "output+no_connect"))
    )
    (net (code "85") (name "unconnected-(U6-D4-Pad5)") (class "Default")
      (node (ref "U6") (pin "5") (pinfunction "D4_5") (pintype "bidirectional"))
    )
    (net (code "86") (name "unconnected-(U6-D5-Pad8)") (class "Default")
      (node (ref "U6") (pin "8") (pinfunction "D5_8") (pintype "bidirectional"))
    )
    (net (code "87") (name "unconnected-(U6-D18-Pad9)") (class "Default")
      (node (ref "U6") (pin "9") (pinfunction "D18_9") (pintype "bidirectional"))
    )
    (net (code "88") (name "unconnected-(U6-D19-Pad10)") (class "Default")
      (node (ref "U6") (pin "10") (pinfunction "D19_10") (pintype "bidirectional"))
    )
    (net (code "89") (name "unconnected-(U6-D22-Pad14)") (class "Default")
      (node (ref "U6") (pin "14") (pinfunction "D22_14") (pintype "bidirectional+no_connect"))
    )
    (net (code "90") (name "unconnected-(U6-D23-Pad15)") (class "Default")
      (node (ref "U6") (pin "15") (pinfunction "D23_15") (pintype "bidirectional+no_connect"))
    )
    (net (code "91") (name "unconnected-(U6-D26-Pad24)") (class "Default")
      (node (ref "U6") (pin "24") (pinfunction "D26_24") (pintype "bidirectional+no_connect"))
    )
    (net (code "92") (name "unconnected-(U6-D27-Pad25)") (class "Default")
      (node (ref "U6") (pin "25") (pinfunction "D27_25") (pintype "bidirectional+no_connect"))
    )
    (net (code "93") (name "unconnected-(U6-D34-Pad19)") (class "Default")
      (node (ref "U6") (pin "19") (pinfunction "D34_19") (pintype "bidirectional+no_connect"))
    )
    (net (code "94") (name "unconnected-(U6-D35-Pad20)") (class "Default")
      (node (ref "U6") (pin "20") (pinfunction "D35_20") (pintype "bidirectional+no_connect"))
    )
    (net (code "95") (name "unconnected-(U6-RX0-Pad12)") (class "Default")
      (node (ref "U6") (pin "12") (pinfunction "RX0_12") (pintype "input+no_connect"))
    )
    (net (code "96") (name "unconnected-(U6-TX0-Pad13)") (class "Default")
      (node (ref "U6") (pin "13") (pinfunction "TX0_13") (pintype "output+no_connect"))
    )
    (net (code "97") (name "unconnected-(U7-3V3-Pad17)") (class "Default")
      (node (ref "U7") (pin "17") (pinfunction "3V3_17") (pintype "power_in"))
    )
    (net (code "98") (name "unconnected-(U7-5V-Pad27)") (class "Default")
      (node (ref "U7") (pin "27") (pinfunction "5V_27") (pintype "power_in"))
    )
    (net (code "99") (name "unconnected-(U7-A1-Pad20)") (class "Default")
      (node (ref "U7") (pin "20") (pinfunction "A1_20") (pintype "input+no_connect"))
    )
    (net (code "100") (name "unconnected-(U7-A2-Pad21)") (class "Default")
      (node (ref "U7") (pin "21") (pinfunction "A2_21") (pintype "input+no_connect"))
    )
    (net (code "101") (name "unconnected-(U7-A3-Pad22)") (class "Default")
      (node (ref "U7") (pin "22") (pinfunction "A3_22") (pintype "input+no_connect"))
    )
    (net (code "102") (name "unconnected-(U7-A4-Pad23)") (class "Default")
      (node (ref "U7") (pin "23") (pinfunction "A4_23") (pintype "input+no_connect"))
    )
    (net (code "103") (name "unconnected-(U7-A5-Pad24)") (class "Default")
      (node (ref "U7") (pin "24") (pinfunction "A5_24") (pintype "input+no_connect"))
    )
    (net (code "104") (name "unconnected-(U7-AREF-Pad18)") (class "Default")
      (node (ref "U7") (pin "18") (pinfunction "AREF_18") (pintype "input+no_connect"))
    )
    (net (code "105") (name "unconnected-(U7-D8-Pad11)") (class "Default")
      (node (ref "U7") (pin "11") (pinfunction "D8_11") (pintype "bidirectional"))
    )
    (net (code "106") (name "unconnected-(U7-D9-Pad12)") (class "Default")
      (node (ref "U7") (pin "12") (pinfunction "D9_12") (pintype "bidirectional"))
    )
    (net (code "107") (name "unconnected-(U7-D13-Pad16)") (class "Default")
      (node (ref "U7") (pin "16") (pinfunction "D13_16") (pintype "bidirectional"))
    )
    (net (code "108") (name "unconnected-(U7-GND_2-Pad29)") (class "Default")
      (node (ref "U7") (pin "29") (pinfunction "GND_2_29") (pintype "power_in"))
    )
    (net (code "109") (name "unconnected-(U7-RESET_1-Pad3)") (class "Default")
      (node (ref "U7") (pin "3") (pinfunction "RESET_1_3") (pintype "input+no_connect"))
    )
    (net (code "110") (name "unconnected-(U7-RESET_2-Pad28)") (class "Default")
      (node (ref "U7") (pin "28") (pinfunction "RESET_2_28") (pintype "input+no_connect"))
    )
  )
)
